# SH3_-_CONNECTORS_2.net
KiCad netlist of a schematic drawn in Altium Designer
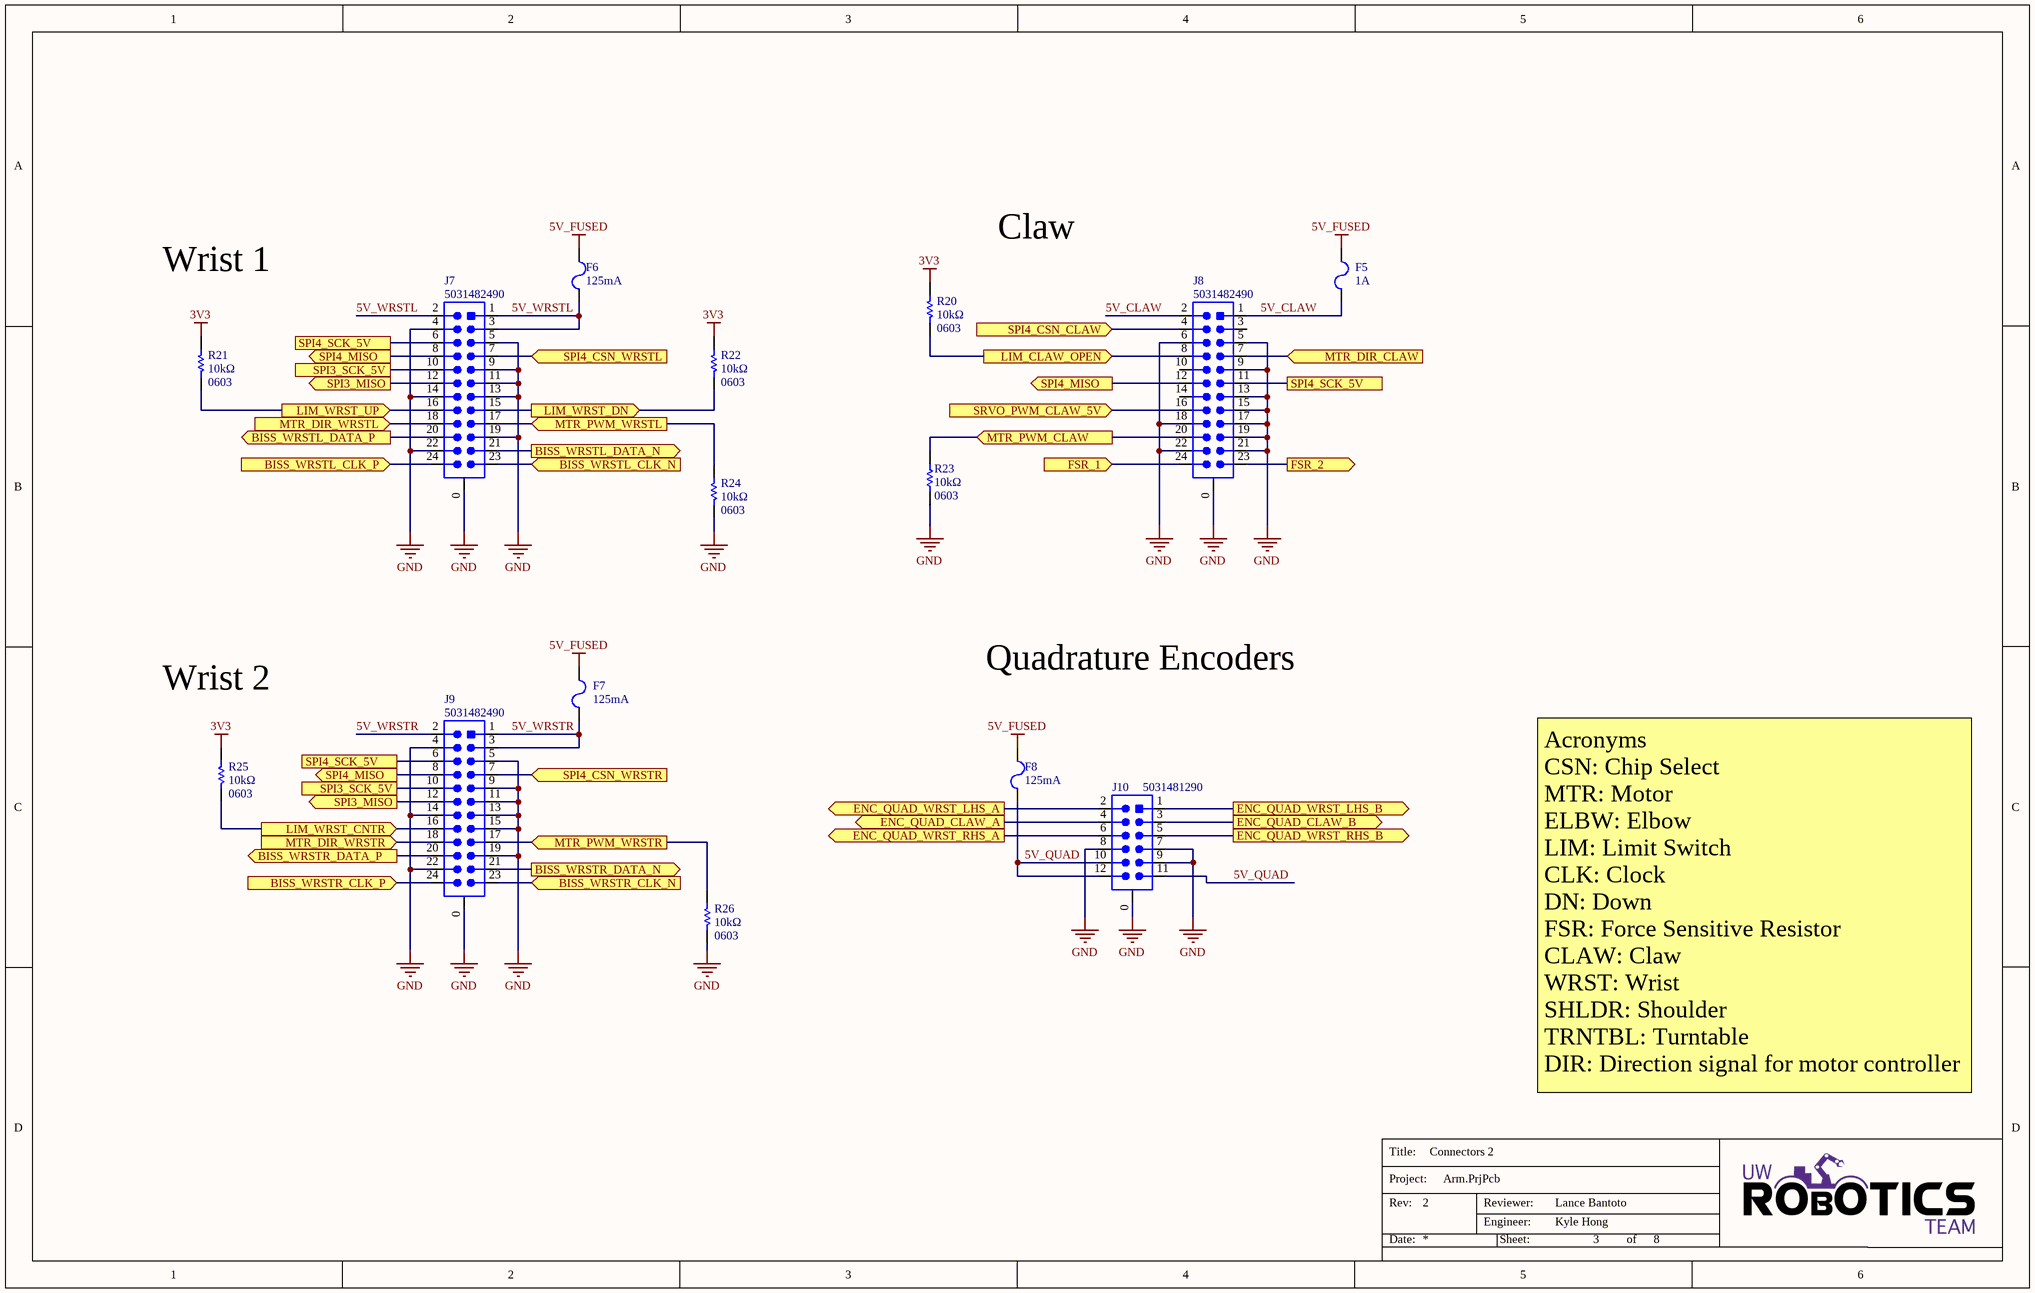
[diagram p0: SH3 - CONNECTORS_2.SchDoc]

(export (version "E")
  (design (tool "Eeschema 10.0.6"))
  (components
    (comp (ref "F5")
      (value "FUSE_1A_1206")
      (footprint "FUSE_1206")
      (description "FUSE BOARD MOUNT 1A 125VAC 63VDC")
      (fields (field (name "CURRENT RATING") "1A"))
      (libsource (lib "UWRT_Schematic_Library_2020") (part "FUSE_1A_1206"))
    )
    (comp (ref "F6")
      (value "FUSE_125mA_1206")
      (footprint "FUSE_1206")
      (description "FUSE BOARD MNT 125MA 125VAC/VDC")
      (fields (field (name "CURRENT RATING") "125mA"))
      (libsource (lib "UWRT_Schematic_Library_2020") (part "FUSE_125mA_1206"))
    )
    (comp (ref "F7")
      (value "FUSE_125mA_1206")
      (footprint "FUSE_1206")
      (description "FUSE BOARD MNT 125MA 125VAC/VDC")
      (fields (field (name "CURRENT RATING") "125mA"))
      (libsource (lib "UWRT_Schematic_Library_2020") (part "FUSE_125mA_1206"))
    )
    (comp (ref "F8")
      (value "FUSE_125mA_1206")
      (footprint "FUSE_1206")
      (description "FUSE BOARD MNT 125MA 125VAC/VDC")
      (fields (field (name "CURRENT RATING") "125mA"))
      (libsource (lib "UWRT_Schematic_Library_2020") (part "FUSE_125mA_1206"))
    )
    (comp (ref "J7")
      (value "CON_12x2M_SM_RA")
      (footprint "MOLEX-5031482490")
      (description "CONN HEADER SMD RIGHT ANGLE 1.5MM PITCH")
      (fields (field (name "MANUFACTURER PART NUMBER 1") "5031482490"))
      (libsource (lib "UWRT_Schematic_Library_2020") (part "CON_12x2M_SM_RA"))
    )
    (comp (ref "J8")
      (value "CON_12x2M_SM_RA")
      (footprint "MOLEX-5031482490")
      (description "CONN HEADER SMD RIGHT ANGLE 1.5MM PITCH")
      (fields (field (name "MANUFACTURER PART NUMBER 1") "5031482490"))
      (libsource (lib "UWRT_Schematic_Library_2020") (part "CON_12x2M_SM_RA"))
    )
    (comp (ref "J9")
      (value "CON_12x2M_SM_RA")
      (footprint "MOLEX-5031482490")
      (description "CONN HEADER SMD RIGHT ANGLE 1.5MM PITCH")
      (fields (field (name "MANUFACTURER PART NUMBER 1") "5031482490"))
      (libsource (lib "UWRT_Schematic_Library_2020") (part "CON_12x2M_SM_RA"))
    )
    (comp (ref "J10")
      (value "CON_6x2M_SM_RA")
      (footprint "MOLEX-5031481290")
      (description "CONN HEADER SMD RIGHT ANGLE 1.5MM PITCH")
      (fields (field (name "MANUFACTURER PART NUMBER 1") "5031481290"))
      (libsource (lib "UWRT_Schematic_Library_2020") (part "CON_6x2M_SM_RA"))
    )
    (comp (ref "R20")
      (value "10kΩ")
      (footprint "RESC0603")
      (description "RES 10K OHM 5% 1/10W 0603")
      (fields (field (name "PACKAGE/FOOTPRINT") "0603") (field (name "Comment") "RES_10kΩ_0603_5%"))
      (libsource (lib "UWRT_Schematic_Library_2020") (part "RES_10kΩ_0603_5%"))
    )
    (comp (ref "R21")
      (value "10kΩ")
      (footprint "RESC0603")
      (description "RES 10K OHM 5% 1/10W 0603")
      (fields (field (name "PACKAGE/FOOTPRINT") "0603") (field (name "Comment") "RES_10kΩ_0603_5%"))
      (libsource (lib "UWRT_Schematic_Library_2020") (part "RES_10kΩ_0603_5%"))
    )
    (comp (ref "R22")
      (value "10kΩ")
      (footprint "RESC0603")
      (description "RES 10K OHM 5% 1/10W 0603")
      (fields (field (name "PACKAGE/FOOTPRINT") "0603") (field (name "Comment") "RES_10kΩ_0603_5%"))
      (libsource (lib "UWRT_Schematic_Library_2020") (part "RES_10kΩ_0603_5%"))
    )
    (comp (ref "R23")
      (value "10kΩ")
      (footprint "RESC0603")
      (description "RES 10K OHM 5% 1/10W 0603")
      (fields (field (name "PACKAGE/FOOTPRINT") "0603") (field (name "Comment") "RES_10kΩ_0603_5%"))
      (libsource (lib "UWRT_Schematic_Library_2020") (part "RES_10kΩ_0603_5%"))
    )
    (comp (ref "R24")
      (value "10kΩ")
      (footprint "RESC0603")
      (description "RES 10K OHM 5% 1/10W 0603")
      (fields (field (name "PACKAGE/FOOTPRINT") "0603") (field (name "Comment") "RES_10kΩ_0603_5%"))
      (libsource (lib "UWRT_Schematic_Library_2020") (part "RES_10kΩ_0603_5%"))
    )
    (comp (ref "R25")
      (value "10kΩ")
      (footprint "RESC0603")
      (description "RES 10K OHM 5% 1/10W 0603")
      (fields (field (name "PACKAGE/FOOTPRINT") "0603") (field (name "Comment") "RES_10kΩ_0603_5%"))
      (libsource (lib "UWRT_Schematic_Library_2020") (part "RES_10kΩ_0603_5%"))
    )
    (comp (ref "R26")
      (value "10kΩ")
      (footprint "RESC0603")
      (description "RES 10K OHM 5% 1/10W 0603")
      (fields (field (name "PACKAGE/FOOTPRINT") "0603") (field (name "Comment") "RES_10kΩ_0603_5%"))
      (libsource (lib "UWRT_Schematic_Library_2020") (part "RES_10kΩ_0603_5%"))
    )
  )
  (nets
    (net (code "1") (name "/5V_CLAW") (class "Default")
      (node (ref "F5") (pin "1") (pinfunction "1_1") (pintype "passive"))
      (node (ref "J8") (pin "1") (pinfunction "1_1") (pintype "passive"))
      (node (ref "J8") (pin "2") (pinfunction "2_2") (pintype "passive"))
    )
    (net (code "2") (name "/5V_QUAD") (class "Default")
      (node (ref "F8") (pin "1") (pinfunction "1_1") (pintype "passive"))
      (node (ref "J10") (pin "10") (pinfunction "10_10") (pintype "passive"))
      (node (ref "J10") (pin "11") (pinfunction "11_11") (pintype "passive"))
      (node (ref "J10") (pin "12") (pinfunction "12_12") (pintype "passive"))
    )
    (net (code "3") (name "/5V_WRSTL") (class "Default")
      (node (ref "F6") (pin "1") (pinfunction "1_1") (pintype "passive"))
      (node (ref "J7") (pin "1") (pinfunction "1_1") (pintype "passive"))
      (node (ref "J7") (pin "2") (pinfunction "2_2") (pintype "passive"))
      (node (ref "J7") (pin "3") (pinfunction "3_3") (pintype "passive"))
    )
    (net (code "4") (name "/5V_WRSTR") (class "Default")
      (node (ref "F7") (pin "1") (pinfunction "1_1") (pintype "passive"))
      (node (ref "J9") (pin "1") (pinfunction "1_1") (pintype "passive"))
      (node (ref "J9") (pin "2") (pinfunction "2_2") (pintype "passive"))
      (node (ref "J9") (pin "3") (pinfunction "3_3") (pintype "passive"))
    )
    (net (code "5") (name "/BISS_WRSTL_CLK_N") (class "Default")
      (node (ref "J7") (pin "23") (pinfunction "23_23") (pintype "passive"))
    )
    (net (code "6") (name "/BISS_WRSTL_CLK_P") (class "Default")
      (node (ref "J7") (pin "24") (pinfunction "24_24") (pintype "passive"))
    )
    (net (code "7") (name "/BISS_WRSTL_DATA_N") (class "Default")
      (node (ref "J7") (pin "21") (pinfunction "21_21") (pintype "passive"))
    )
    (net (code "8") (name "/BISS_WRSTL_DATA_P") (class "Default")
      (node (ref "J7") (pin "20") (pinfunction "20_20") (pintype "passive"))
    )
    (net (code "9") (name "/BISS_WRSTR_CLK_N") (class "Default")
      (node (ref "J9") (pin "23") (pinfunction "23_23") (pintype "passive"))
    )
    (net (code "10") (name "/BISS_WRSTR_CLK_P") (class "Default")
      (node (ref "J9") (pin "24") (pinfunction "24_24") (pintype "passive"))
    )
    (net (code "11") (name "/BISS_WRSTR_DATA_N") (class "Default")
      (node (ref "J9") (pin "21") (pinfunction "21_21") (pintype "passive"))
    )
    (net (code "12") (name "/BISS_WRSTR_DATA_P") (class "Default")
      (node (ref "J9") (pin "20") (pinfunction "20_20") (pintype "passive"))
    )
    (net (code "13") (name "/ENC_QUAD_CLAW_A") (class "Default")
      (node (ref "J10") (pin "4") (pinfunction "4_4") (pintype "passive"))
    )
    (net (code "14") (name "/ENC_QUAD_CLAW_B") (class "Default")
      (node (ref "J10") (pin "3") (pinfunction "3_3") (pintype "passive"))
    )
    (net (code "15") (name "/ENC_QUAD_WRST_LHS_A") (class "Default")
      (node (ref "J10") (pin "2") (pinfunction "2_2") (pintype "passive"))
    )
    (net (code "16") (name "/ENC_QUAD_WRST_LHS_B") (class "Default")
      (node (ref "J10") (pin "1") (pinfunction "1_1") (pintype "passive"))
    )
    (net (code "17") (name "/ENC_QUAD_WRST_RHS_A") (class "Default")
      (node (ref "J10") (pin "6") (pinfunction "6_6") (pintype "passive"))
    )
    (net (code "18") (name "/ENC_QUAD_WRST_RHS_B") (class "Default")
      (node (ref "J10") (pin "5") (pinfunction "5_5") (pintype "passive"))
    )
    (net (code "19") (name "/FSR_1") (class "Default")
      (node (ref "J8") (pin "24") (pinfunction "24_24") (pintype "passive"))
    )
    (net (code "20") (name "/FSR_2") (class "Default")
      (node (ref "J8") (pin "23") (pinfunction "23_23") (pintype "passive"))
    )
    (net (code "21") (name "/LIM_CLAW_OPEN") (class "Default")
      (node (ref "J8") (pin "8") (pinfunction "8_8") (pintype "passive"))
      (node (ref "R20") (pin "1") (pinfunction "1_1") (pintype "passive"))
    )
    (net (code "22") (name "/LIM_WRST_CNTR") (class "Default")
      (node (ref "J9") (pin "16") (pinfunction "16_16") (pintype "passive"))
      (node (ref "R25") (pin "1") (pinfunction "1_1") (pintype "passive"))
    )
    (net (code "23") (name "/LIM_WRST_DN") (class "Default")
      (node (ref "J7") (pin "15") (pinfunction "15_15") (pintype "passive"))
      (node (ref "R22") (pin "1") (pinfunction "1_1") (pintype "passive"))
    )
    (net (code "24") (name "/LIM_WRST_UP") (class "Default")
      (node (ref "J7") (pin "16") (pinfunction "16_16") (pintype "passive"))
      (node (ref "R21") (pin "1") (pinfunction "1_1") (pintype "passive"))
    )
    (net (code "25") (name "/MTR_DIR_CLAW") (class "Default")
      (node (ref "J8") (pin "7") (pinfunction "7_7") (pintype "passive"))
    )
    (net (code "26") (name "/MTR_DIR_WRSTL") (class "Default")
      (node (ref "J7") (pin "18") (pinfunction "18_18") (pintype "passive"))
    )
    (net (code "27") (name "/MTR_DIR_WRSTR") (class "Default")
      (node (ref "J9") (pin "18") (pinfunction "18_18") (pintype "passive"))
    )
    (net (code "28") (name "/MTR_PWM_CLAW") (class "Default")
      (node (ref "J8") (pin "20") (pinfunction "20_20") (pintype "passive"))
      (node (ref "R23") (pin "2") (pinfunction "2_2") (pintype "passive"))
    )
    (net (code "29") (name "/MTR_PWM_WRSTL") (class "Default")
      (node (ref "J7") (pin "17") (pinfunction "17_17") (pintype "passive"))
      (node (ref "R24") (pin "2") (pinfunction "2_2") (pintype "passive"))
    )
    (net (code "30") (name "/MTR_PWM_WRSTR") (class "Default")
      (node (ref "J9") (pin "17") (pinfunction "17_17") (pintype "passive"))
      (node (ref "R26") (pin "2") (pinfunction "2_2") (pintype "passive"))
    )
    (net (code "31") (name "/SPI3_MISO") (class "Default")
      (node (ref "J7") (pin "12") (pinfunction "12_12") (pintype "passive"))
      (node (ref "J9") (pin "12") (pinfunction "12_12") (pintype "passive"))
    )
    (net (code "32") (name "/SPI3_SCK_5V") (class "Default")
      (node (ref "J7") (pin "10") (pinfunction "10_10") (pintype "passive"))
      (node (ref "J9") (pin "10") (pinfunction "10_10") (pintype "passive"))
    )
    (net (code "33") (name "/SPI4_CSN_CLAW") (class "Default")
      (node (ref "J8") (pin "4") (pinfunction "4_4") (pintype "passive"))
    )
    (net (code "34") (name "/SPI4_CSN_WRSTL") (class "Default")
      (node (ref "J7") (pin "7") (pinfunction "7_7") (pintype "passive"))
    )
    (net (code "35") (name "/SPI4_CSN_WRSTR") (class "Default")
      (node (ref "J9") (pin "7") (pinfunction "7_7") (pintype "passive"))
    )
    (net (code "36") (name "/SPI4_MISO") (class "Default")
      (node (ref "J7") (pin "8") (pinfunction "8_8") (pintype "passive"))
      (node (ref "J8") (pin "12") (pinfunction "12_12") (pintype "passive"))
      (node (ref "J9") (pin "8") (pinfunction "8_8") (pintype "passive"))
    )
    (net (code "37") (name "/SPI4_SCK_5V") (class "Default")
      (node (ref "J7") (pin "6") (pinfunction "6_6") (pintype "passive"))
      (node (ref "J8") (pin "11") (pinfunction "11_11") (pintype "passive"))
      (node (ref "J9") (pin "6") (pinfunction "6_6") (pintype "passive"))
    )
    (net (code "38") (name "/SRVO_PWM_CLAW_5V") (class "Default")
      (node (ref "J8") (pin "16") (pinfunction "16_16") (pintype "passive"))
    )
    (net (code "39") (name "3V3") (class "Default")
      (node (ref "R20") (pin "2") (pinfunction "2_2") (pintype "passive"))
      (node (ref "R21") (pin "2") (pinfunction "2_2") (pintype "passive"))
      (node (ref "R22") (pin "2") (pinfunction "2_2") (pintype "passive"))
      (node (ref "R25") (pin "2") (pinfunction "2_2") (pintype "passive"))
    )
    (net (code "40") (name "5V_FUSED") (class "Default")
      (node (ref "F5") (pin "2") (pinfunction "2_2") (pintype "passive"))
      (node (ref "F6") (pin "2") (pinfunction "2_2") (pintype "passive"))
      (node (ref "F7") (pin "2") (pinfunction "2_2") (pintype "passive"))
      (node (ref "F8") (pin "2") (pinfunction "2_2") (pintype "passive"))
    )
    (net (code "41") (name "GND") (class "Default")
      (node (ref "J10") (pin "0") (pinfunction "0_0") (pintype "passive"))
      (node (ref "J10") (pin "7") (pinfunction "7_7") (pintype "passive"))
      (node (ref "J10") (pin "8") (pinfunction "8_8") (pintype "passive"))
      (node (ref "J10") (pin "9") (pinfunction "9_9") (pintype "passive"))
      (node (ref "J7") (pin "0") (pinfunction "0_0") (pintype "passive"))
      (node (ref "J7") (pin "11") (pinfunction "11_11") (pintype "passive"))
      (node (ref "J7") (pin "13") (pinfunction "13_13") (pintype "passive"))
      (node (ref "J7") (pin "14") (pinfunction "14_14") (pintype "passive"))
      (node (ref "J7") (pin "19") (pinfunction "19_19") (pintype "passive"))
      (node (ref "J7") (pin "22") (pinfunction "22_22") (pintype "passive"))
      (node (ref "J7") (pin "4") (pinfunction "4_4") (pintype "passive"))
      (node (ref "J7") (pin "5") (pinfunction "5_5") (pintype "passive"))
      (node (ref "J7") (pin "9") (pinfunction "9_9") (pintype "passive"))
      (node (ref "J8") (pin "0") (pinfunction "0_0") (pintype "passive"))
      (node (ref "J8") (pin "13") (pinfunction "13_13") (pintype "passive"))
      (node (ref "J8") (pin "15") (pinfunction "15_15") (pintype "passive"))
      (node (ref "J8") (pin "17") (pinfunction "17_17") (pintype "passive"))
      (node (ref "J8") (pin "18") (pinfunction "18_18") (pintype "passive"))
      (node (ref "J8") (pin "19") (pinfunction "19_19") (pintype "passive"))
      (node (ref "J8") (pin "21") (pinfunction "21_21") (pintype "passive"))
      (node (ref "J8") (pin "22") (pinfunction "22_22") (pintype "passive"))
      (node (ref "J8") (pin "5") (pinfunction "5_5") (pintype "passive"))
      (node (ref "J8") (pin "6") (pinfunction "6_6") (pintype "passive"))
      (node (ref "J8") (pin "9") (pinfunction "9_9") (pintype "passive"))
      (node (ref "J9") (pin "0") (pinfunction "0_0") (pintype "passive"))
      (node (ref "J9") (pin "11") (pinfunction "11_11") (pintype "passive"))
      (node (ref "J9") (pin "13") (pinfunction "13_13") (pintype "passive"))
      (node (ref "J9") (pin "14") (pinfunction "14_14") (pintype "passive"))
      (node (ref "J9") (pin "15") (pinfunction "15_15") (pintype "passive"))
      (node (ref "J9") (pin "19") (pinfunction "19_19") (pintype "passive"))
      (node (ref "J9") (pin "22") (pinfunction "22_22") (pintype "passive"))
      (node (ref "J9") (pin "4") (pinfunction "4_4") (pintype "passive"))
      (node (ref "J9") (pin "5") (pinfunction "5_5") (pintype "passive"))
      (node (ref "J9") (pin "9") (pinfunction "9_9") (pintype "passive"))
      (node (ref "R23") (pin "1") (pinfunction "1_1") (pintype "passive"))
      (node (ref "R24") (pin "1") (pinfunction "1_1") (pintype "passive"))
      (node (ref "R26") (pin "1") (pinfunction "1_1") (pintype "passive"))
    )
    (net (code "42") (name "unconnected-(J8-Pad3)") (class "Default")
      (node (ref "J8") (pin "3") (pinfunction "3_3") (pintype "passive"))
    )
    (net (code "43") (name "unconnected-(J8-Pad10)") (class "Default")
      (node (ref "J8") (pin "10") (pinfunction "10_10") (pintype "passive"))
    )
    (net (code "44") (name "unconnected-(J8-Pad14)") (class "Default")
      (node (ref "J8") (pin "14") (pinfunction "14_14") (pintype "passive"))
    )
  )
)
